# relaxbox.net
KiCad netlist of a schematic drawn in EAGLE
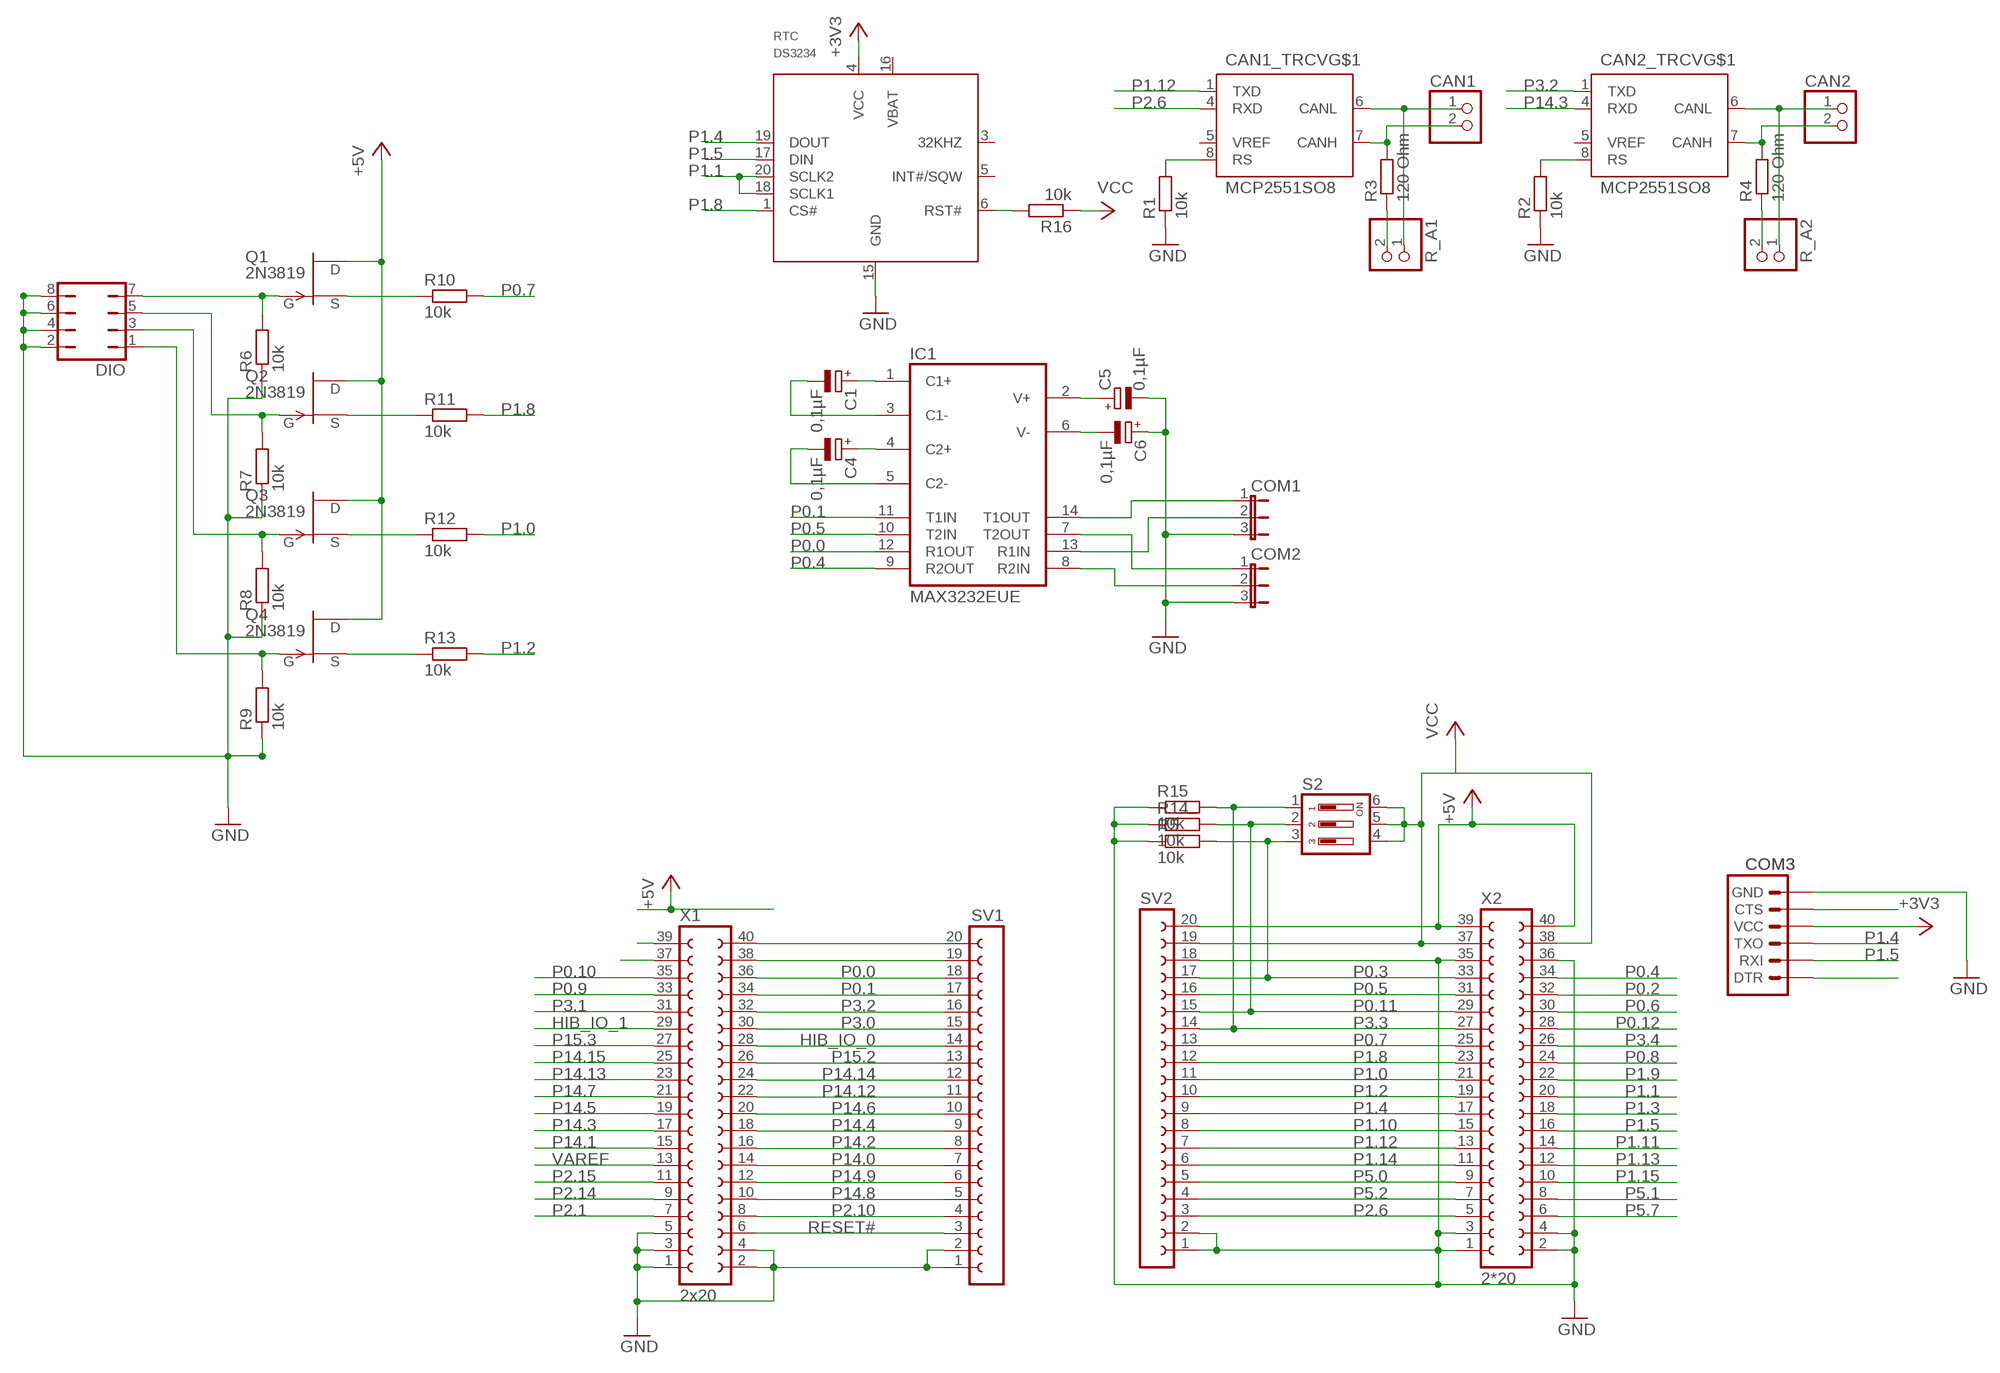
[diagram p0: schematic, sheet 1]

(export (version "E")
  (design (tool "Eeschema 10.0.6"))
  (components
    (comp (ref "C1")
      (value "0,1µF")
      (footprint "eagle-import:E2,5-5")
      (libsource (lib "eagle-import") (part "CPOL-EUE2.5-5"))
    )
    (comp (ref "C4")
      (value "0,1µF")
      (footprint "eagle-import:E2,5-5")
      (libsource (lib "eagle-import") (part "CPOL-EUE2.5-5"))
    )
    (comp (ref "C5")
      (value "0,1µF")
      (footprint "eagle-import:E2,5-5")
      (libsource (lib "eagle-import") (part "CPOL-EUE2.5-5"))
    )
    (comp (ref "C6")
      (value "0,1µF")
      (footprint "eagle-import:E2,5-5")
      (libsource (lib "eagle-import") (part "CPOL-EUE2.5-5"))
    )
    (comp (ref "CAN1")
      (value "PINHD-1X2")
      (footprint "eagle-import:1X02")
      (libsource (lib "eagle-import") (part "PINHD-1X2"))
    )
    (comp (ref "CAN1_TRCV")
      (value "MCP2551SO8")
      (footprint "eagle-import:SO08")
      (libsource (lib "eagle-import") (part "MCP2551SO8"))
    )
    (comp (ref "CAN2")
      (value "PINHD-1X2")
      (footprint "eagle-import:1X02")
      (libsource (lib "eagle-import") (part "PINHD-1X2"))
    )
    (comp (ref "CAN2_TRCV")
      (value "MCP2551SO8")
      (footprint "eagle-import:SO08")
      (libsource (lib "eagle-import") (part "MCP2551SO8"))
    )
    (comp (ref "COM1")
      (value "JP2E")
      (footprint "eagle-import:JP2")
      (libsource (lib "eagle-import") (part "JP2E"))
    )
    (comp (ref "COM2")
      (value "JP2E")
      (footprint "eagle-import:JP2")
      (libsource (lib "eagle-import") (part "JP2E"))
    )
    (comp (ref "COM3")
      (value "SPARKFUN_ARDUINO_SERIAL_PROGRAMPTH")
      (footprint "eagle-import:SPARKFUN_1X06")
      (libsource (lib "eagle-import") (part "SPARKFUN_ARDUINO_SERIAL_PROGRAMPTH"))
    )
    (comp (ref "DIO")
      (value "JP4Q")
      (footprint "eagle-import:JP4Q")
      (libsource (lib "eagle-import") (part "JP4Q"))
    )
    (comp (ref "IC1")
      (value "MAX3232EUE")
      (footprint "eagle-import:TSSOP16")
      (fields (field (name "MF") "MAXIM") (field (name "MPN") "MAX3232EUE+"))
      (libsource (lib "eagle-import") (part "MAX3232UEE"))
    )
    (comp (ref "Q1")
      (value "2N3819")
      (footprint "eagle-import:TO92")
      (libsource (lib "eagle-import") (part "2N3819"))
    )
    (comp (ref "Q2")
      (value "2N3819")
      (footprint "eagle-import:TO92")
      (libsource (lib "eagle-import") (part "2N3819"))
    )
    (comp (ref "Q3")
      (value "2N3819")
      (footprint "eagle-import:TO92")
      (libsource (lib "eagle-import") (part "2N3819"))
    )
    (comp (ref "Q4")
      (value "2N3819")
      (footprint "eagle-import:TO92")
      (libsource (lib "eagle-import") (part "2N3819"))
    )
    (comp (ref "R1")
      (value "10k")
      (footprint "eagle-import:M0805")
      (libsource (lib "eagle-import") (part "R-EU_M0805"))
    )
    (comp (ref "R2")
      (value "10k")
      (footprint "eagle-import:M0805")
      (libsource (lib "eagle-import") (part "R-EU_M0805"))
    )
    (comp (ref "R3")
      (value "120 Ohm")
      (footprint "eagle-import:M0805")
      (libsource (lib "eagle-import") (part "R-EU_M0805"))
    )
    (comp (ref "R4")
      (value "120 Ohm")
      (footprint "eagle-import:M0805")
      (libsource (lib "eagle-import") (part "R-EU_M0805"))
    )
    (comp (ref "R5")
      (value "10k")
      (footprint "eagle-import:M0805")
      (libsource (lib "eagle-import") (part "R-EU_M0805"))
    )
    (comp (ref "R6")
      (value "10k")
      (footprint "eagle-import:M0805")
      (libsource (lib "eagle-import") (part "R-EU_M0805"))
    )
    (comp (ref "R7")
      (value "10k")
      (footprint "eagle-import:M0805")
      (libsource (lib "eagle-import") (part "R-EU_M0805"))
    )
    (comp (ref "R8")
      (value "10k")
      (footprint "eagle-import:M0805")
      (libsource (lib "eagle-import") (part "R-EU_M0805"))
    )
    (comp (ref "R9")
      (value "10k")
      (footprint "eagle-import:M0805")
      (libsource (lib "eagle-import") (part "R-EU_M0805"))
    )
    (comp (ref "R10")
      (value "10k")
      (footprint "eagle-import:M0805")
      (libsource (lib "eagle-import") (part "R-EU_M0805"))
    )
    (comp (ref "R11")
      (value "10k")
      (footprint "eagle-import:M0805")
      (libsource (lib "eagle-import") (part "R-EU_M0805"))
    )
    (comp (ref "R12")
      (value "10k")
      (footprint "eagle-import:M0805")
      (libsource (lib "eagle-import") (part "R-EU_M0805"))
    )
    (comp (ref "R13")
      (value "10k")
      (footprint "eagle-import:M0805")
      (libsource (lib "eagle-import") (part "R-EU_M0805"))
    )
    (comp (ref "R14")
      (value "10k")
      (footprint "eagle-import:M0805")
      (libsource (lib "eagle-import") (part "R-EU_M0805"))
    )
    (comp (ref "R15")
      (value "10k")
      (footprint "eagle-import:M0805")
      (libsource (lib "eagle-import") (part "R-EU_M0805"))
    )
    (comp (ref "R16")
      (value "10k")
      (footprint "eagle-import:M0805")
      (libsource (lib "eagle-import") (part "R-EU_M0805"))
    )
    (comp (ref "RTC")
      (value "DS3234")
      (footprint "eagle-import:SO-20DW")
      (libsource (lib "eagle-import") (part "DS3234"))
    )
    (comp (ref "R_A1")
      (value "PINHD-1X2")
      (footprint "eagle-import:1X02")
      (libsource (lib "eagle-import") (part "PINHD-1X2"))
    )
    (comp (ref "R_A2")
      (value "PINHD-1X2")
      (footprint "eagle-import:1X02")
      (libsource (lib "eagle-import") (part "PINHD-1X2"))
    )
    (comp (ref "S2")
      (value "DIP03YL")
      (footprint "eagle-import:DIP03YL")
      (libsource (lib "eagle-import") (part "DIP03YL"))
    )
    (comp (ref "SV1")
      (value "FE20-1")
      (footprint "eagle-import:FE20")
      (libsource (lib "eagle-import") (part "FE20-1"))
    )
    (comp (ref "SV2")
      (value "FE20-1")
      (footprint "eagle-import:FE20")
      (libsource (lib "eagle-import") (part "FE20-1"))
    )
    (comp (ref "X1")
      (value "2x20")
      (footprint "eagle-import:FE20-2")
      (libsource (lib "eagle-import") (part "FE20-2"))
    )
    (comp (ref "X2")
      (value "2*20")
      (footprint "eagle-import:FE20-2")
      (libsource (lib "eagle-import") (part "FE20-2"))
    )
  )
  (nets
    (net (code "1") (name "+3V3") (class "Default")
      (node (ref "COM3") (pin "4") (pinfunction "VCC_4") (pintype "passive"))
      (node (ref "RTC") (pin "4") (pinfunction "VCC_4") (pintype "bidirectional"))
    )
    (net (code "2") (name "+5V") (class "Default")
      (node (ref "Q1") (pin "1") (pinfunction "D_1") (pintype "passive"))
      (node (ref "Q2") (pin "1") (pinfunction "D_1") (pintype "passive"))
      (node (ref "Q3") (pin "1") (pinfunction "D_1") (pintype "passive"))
      (node (ref "Q4") (pin "1") (pinfunction "D_1") (pintype "passive"))
      (node (ref "SV2") (pin "20") (pinfunction "20_20") (pintype "passive"))
      (node (ref "X2") (pin "39") (pinfunction "39_39") (pintype "passive"))
      (node (ref "X2") (pin "40") (pinfunction "40_40") (pintype "passive"))
    )
    (net (code "3") (name "/HIB_IO_0") (class "Default")
      (node (ref "SV1") (pin "14") (pinfunction "14_14") (pintype "passive"))
      (node (ref "X1") (pin "28") (pinfunction "28_28") (pintype "passive"))
    )
    (net (code "4") (name "/HIB_IO_1") (class "Default")
      (node (ref "X1") (pin "29") (pinfunction "29_29") (pintype "passive"))
    )
    (net (code "5") (name "/P0.0") (class "Default")
      (node (ref "IC1") (pin "12") (pinfunction "R1OUT_12") (pintype "output"))
      (node (ref "SV1") (pin "18") (pinfunction "18_18") (pintype "passive"))
      (node (ref "X1") (pin "36") (pinfunction "36_36") (pintype "passive"))
    )
    (net (code "6") (name "/P0.1") (class "Default")
      (node (ref "IC1") (pin "11") (pinfunction "T1IN_11") (pintype "input"))
      (node (ref "SV1") (pin "17") (pinfunction "17_17") (pintype "passive"))
      (node (ref "X1") (pin "34") (pinfunction "34_34") (pintype "passive"))
    )
    (net (code "7") (name "/P0.2") (class "Default")
      (node (ref "X2") (pin "32") (pinfunction "32_32") (pintype "passive"))
    )
    (net (code "8") (name "/P0.3") (class "Default")
      (node (ref "R5") (pin "2") (pinfunction "2_2") (pintype "passive"))
      (node (ref "S2") (pin "3") (pinfunction "3_3") (pintype "passive"))
      (node (ref "SV2") (pin "17") (pinfunction "17_17") (pintype "passive"))
      (node (ref "X2") (pin "33") (pinfunction "33_33") (pintype "passive"))
    )
    (net (code "9") (name "/P0.4") (class "Default")
      (node (ref "IC1") (pin "9") (pinfunction "R2OUT_9") (pintype "output"))
      (node (ref "X2") (pin "34") (pinfunction "34_34") (pintype "passive"))
    )
    (net (code "10") (name "/P0.5") (class "Default")
      (node (ref "IC1") (pin "10") (pinfunction "T2IN_10") (pintype "input"))
      (node (ref "SV2") (pin "16") (pinfunction "16_16") (pintype "passive"))
      (node (ref "X2") (pin "31") (pinfunction "31_31") (pintype "passive"))
    )
    (net (code "11") (name "/P0.6") (class "Default")
      (node (ref "X2") (pin "30") (pinfunction "30_30") (pintype "passive"))
    )
    (net (code "12") (name "/P0.7") (class "Default")
      (node (ref "R10") (pin "2") (pinfunction "2_2") (pintype "passive"))
      (node (ref "SV2") (pin "13") (pinfunction "13_13") (pintype "passive"))
      (node (ref "X2") (pin "25") (pinfunction "25_25") (pintype "passive"))
    )
    (net (code "13") (name "/P0.8") (class "Default")
      (node (ref "X2") (pin "24") (pinfunction "24_24") (pintype "passive"))
    )
    (net (code "14") (name "/P0.9") (class "Default")
      (node (ref "X1") (pin "33") (pinfunction "33_33") (pintype "passive"))
    )
    (net (code "15") (name "/P0.10") (class "Default")
      (node (ref "X1") (pin "35") (pinfunction "35_35") (pintype "passive"))
    )
    (net (code "16") (name "/P0.11") (class "Default")
      (node (ref "R14") (pin "2") (pinfunction "2_2") (pintype "passive"))
      (node (ref "S2") (pin "2") (pinfunction "2_2") (pintype "passive"))
      (node (ref "SV2") (pin "15") (pinfunction "15_15") (pintype "passive"))
      (node (ref "X2") (pin "29") (pinfunction "29_29") (pintype "passive"))
    )
    (net (code "17") (name "/P0.12") (class "Default")
      (node (ref "X2") (pin "28") (pinfunction "28_28") (pintype "passive"))
    )
    (net (code "18") (name "/P1.0") (class "Default")
      (node (ref "R12") (pin "2") (pinfunction "2_2") (pintype "passive"))
      (node (ref "SV2") (pin "11") (pinfunction "11_11") (pintype "passive"))
      (node (ref "X2") (pin "21") (pinfunction "21_21") (pintype "passive"))
    )
    (net (code "19") (name "/P1.1") (class "Default")
      (node (ref "RTC") (pin "18") (pinfunction "SCLK1_18") (pintype "bidirectional"))
      (node (ref "RTC") (pin "20") (pinfunction "SCLK2_20") (pintype "bidirectional"))
      (node (ref "X2") (pin "20") (pinfunction "20_20") (pintype "passive"))
    )
    (net (code "20") (name "/P1.2") (class "Default")
      (node (ref "R13") (pin "2") (pinfunction "2_2") (pintype "passive"))
      (node (ref "SV2") (pin "10") (pinfunction "10_10") (pintype "passive"))
      (node (ref "X2") (pin "19") (pinfunction "19_19") (pintype "passive"))
    )
    (net (code "21") (name "/P1.3") (class "Default")
      (node (ref "X2") (pin "18") (pinfunction "18_18") (pintype "passive"))
    )
    (net (code "22") (name "/P1.4") (class "Default")
      (node (ref "COM3") (pin "3") (pinfunction "TXO_3") (pintype "passive"))
      (node (ref "RTC") (pin "19") (pinfunction "DOUT_19") (pintype "bidirectional"))
      (node (ref "SV2") (pin "9") (pinfunction "9_9") (pintype "passive"))
      (node (ref "X2") (pin "17") (pinfunction "17_17") (pintype "passive"))
    )
    (net (code "23") (name "/P1.5") (class "Default")
      (node (ref "COM3") (pin "2") (pinfunction "RXI_2") (pintype "passive"))
      (node (ref "RTC") (pin "17") (pinfunction "DIN_17") (pintype "bidirectional"))
      (node (ref "X2") (pin "16") (pinfunction "16_16") (pintype "passive"))
    )
    (net (code "24") (name "/P1.8") (class "Default")
      (node (ref "R11") (pin "2") (pinfunction "2_2") (pintype "passive"))
      (node (ref "RTC") (pin "1") (pinfunction "CS#_1") (pintype "bidirectional"))
      (node (ref "SV2") (pin "12") (pinfunction "12_12") (pintype "passive"))
      (node (ref "X2") (pin "23") (pinfunction "23_23") (pintype "passive"))
    )
    (net (code "25") (name "/P1.9") (class "Default")
      (node (ref "X2") (pin "22") (pinfunction "22_22") (pintype "passive"))
    )
    (net (code "26") (name "/P1.10") (class "Default")
      (node (ref "SV2") (pin "8") (pinfunction "8_8") (pintype "passive"))
      (node (ref "X2") (pin "15") (pinfunction "15_15") (pintype "passive"))
    )
    (net (code "27") (name "/P1.11") (class "Default")
      (node (ref "X2") (pin "14") (pinfunction "14_14") (pintype "passive"))
    )
    (net (code "28") (name "/P1.12") (class "Default")
      (node (ref "CAN1_TRCV") (pin "1") (pinfunction "TXD_1") (pintype "bidirectional"))
      (node (ref "SV2") (pin "7") (pinfunction "7_7") (pintype "passive"))
      (node (ref "X2") (pin "13") (pinfunction "13_13") (pintype "passive"))
    )
    (net (code "29") (name "/P1.13") (class "Default")
      (node (ref "X2") (pin "12") (pinfunction "12_12") (pintype "passive"))
    )
    (net (code "30") (name "/P1.14") (class "Default")
      (node (ref "SV2") (pin "6") (pinfunction "6_6") (pintype "passive"))
      (node (ref "X2") (pin "11") (pinfunction "11_11") (pintype "passive"))
    )
    (net (code "31") (name "/P1.15") (class "Default")
      (node (ref "X2") (pin "10") (pinfunction "10_10") (pintype "passive"))
    )
    (net (code "32") (name "/P2.1") (class "Default")
      (node (ref "X1") (pin "7") (pinfunction "7_7") (pintype "passive"))
    )
    (net (code "33") (name "/P2.6") (class "Default")
      (node (ref "CAN1_TRCV") (pin "4") (pinfunction "RXD_4") (pintype "bidirectional"))
      (node (ref "SV2") (pin "3") (pinfunction "3_3") (pintype "passive"))
      (node (ref "X2") (pin "5") (pinfunction "5_5") (pintype "passive"))
    )
    (net (code "34") (name "/P2.10") (class "Default")
      (node (ref "SV1") (pin "4") (pinfunction "4_4") (pintype "passive"))
      (node (ref "X1") (pin "8") (pinfunction "8_8") (pintype "passive"))
    )
    (net (code "35") (name "/P2.14") (class "Default")
      (node (ref "X1") (pin "9") (pinfunction "9_9") (pintype "passive"))
    )
    (net (code "36") (name "/P2.15") (class "Default")
      (node (ref "X1") (pin "11") (pinfunction "11_11") (pintype "passive"))
    )
    (net (code "37") (name "/P3.0") (class "Default")
      (node (ref "SV1") (pin "15") (pinfunction "15_15") (pintype "passive"))
      (node (ref "X1") (pin "30") (pinfunction "30_30") (pintype "passive"))
    )
    (net (code "38") (name "/P3.1") (class "Default")
      (node (ref "X1") (pin "31") (pinfunction "31_31") (pintype "passive"))
    )
    (net (code "39") (name "/P3.2") (class "Default")
      (node (ref "CAN2_TRCV") (pin "1") (pinfunction "TXD_1") (pintype "bidirectional"))
      (node (ref "SV1") (pin "16") (pinfunction "16_16") (pintype "passive"))
      (node (ref "X1") (pin "32") (pinfunction "32_32") (pintype "passive"))
    )
    (net (code "40") (name "/P3.3") (class "Default")
      (node (ref "R15") (pin "2") (pinfunction "2_2") (pintype "passive"))
      (node (ref "S2") (pin "1") (pinfunction "1_1") (pintype "passive"))
      (node (ref "SV2") (pin "14") (pinfunction "14_14") (pintype "passive"))
      (node (ref "X2") (pin "27") (pinfunction "27_27") (pintype "passive"))
    )
    (net (code "41") (name "/P3.4") (class "Default")
      (node (ref "X2") (pin "26") (pinfunction "26_26") (pintype "passive"))
    )
    (net (code "42") (name "/P5.0") (class "Default")
      (node (ref "SV2") (pin "5") (pinfunction "5_5") (pintype "passive"))
      (node (ref "X2") (pin "9") (pinfunction "9_9") (pintype "passive"))
    )
    (net (code "43") (name "/P5.1") (class "Default")
      (node (ref "X2") (pin "8") (pinfunction "8_8") (pintype "passive"))
    )
    (net (code "44") (name "/P5.2") (class "Default")
      (node (ref "SV2") (pin "4") (pinfunction "4_4") (pintype "passive"))
      (node (ref "X2") (pin "7") (pinfunction "7_7") (pintype "passive"))
    )
    (net (code "45") (name "/P5.7") (class "Default")
      (node (ref "X2") (pin "6") (pinfunction "6_6") (pintype "passive"))
    )
    (net (code "46") (name "/P14.0") (class "Default")
      (node (ref "SV1") (pin "7") (pinfunction "7_7") (pintype "passive"))
      (node (ref "X1") (pin "14") (pinfunction "14_14") (pintype "passive"))
    )
    (net (code "47") (name "/P14.1") (class "Default")
      (node (ref "X1") (pin "15") (pinfunction "15_15") (pintype "passive"))
    )
    (net (code "48") (name "/P14.2") (class "Default")
      (node (ref "SV1") (pin "8") (pinfunction "8_8") (pintype "passive"))
      (node (ref "X1") (pin "16") (pinfunction "16_16") (pintype "passive"))
    )
    (net (code "49") (name "/P14.3") (class "Default")
      (node (ref "CAN2_TRCV") (pin "4") (pinfunction "RXD_4") (pintype "bidirectional"))
      (node (ref "X1") (pin "17") (pinfunction "17_17") (pintype "passive"))
    )
    (net (code "50") (name "/P14.4") (class "Default")
      (node (ref "SV1") (pin "9") (pinfunction "9_9") (pintype "passive"))
      (node (ref "X1") (pin "18") (pinfunction "18_18") (pintype "passive"))
    )
    (net (code "51") (name "/P14.5") (class "Default")
      (node (ref "X1") (pin "19") (pinfunction "19_19") (pintype "passive"))
    )
    (net (code "52") (name "/P14.6") (class "Default")
      (node (ref "SV1") (pin "10") (pinfunction "10_10") (pintype "passive"))
      (node (ref "X1") (pin "20") (pinfunction "20_20") (pintype "passive"))
    )
    (net (code "53") (name "/P14.7") (class "Default")
      (node (ref "X1") (pin "21") (pinfunction "21_21") (pintype "passive"))
    )
    (net (code "54") (name "/P14.8") (class "Default")
      (node (ref "SV1") (pin "5") (pinfunction "5_5") (pintype "passive"))
      (node (ref "X1") (pin "10") (pinfunction "10_10") (pintype "passive"))
    )
    (net (code "55") (name "/P14.9") (class "Default")
      (node (ref "SV1") (pin "6") (pinfunction "6_6") (pintype "passive"))
      (node (ref "X1") (pin "12") (pinfunction "12_12") (pintype "passive"))
    )
    (net (code "56") (name "/P14.12") (class "Default")
      (node (ref "SV1") (pin "11") (pinfunction "11_11") (pintype "passive"))
      (node (ref "X1") (pin "22") (pinfunction "22_22") (pintype "passive"))
    )
    (net (code "57") (name "/P14.13") (class "Default")
      (node (ref "X1") (pin "23") (pinfunction "23_23") (pintype "passive"))
    )
    (net (code "58") (name "/P14.14") (class "Default")
      (node (ref "SV1") (pin "12") (pinfunction "12_12") (pintype "passive"))
      (node (ref "X1") (pin "24") (pinfunction "24_24") (pintype "passive"))
    )
    (net (code "59") (name "/P14.15") (class "Default")
      (node (ref "X1") (pin "25") (pinfunction "25_25") (pintype "passive"))
    )
    (net (code "60") (name "/P15.2") (class "Default")
      (node (ref "SV1") (pin "13") (pinfunction "13_13") (pintype "passive"))
      (node (ref "X1") (pin "26") (pinfunction "26_26") (pintype "passive"))
    )
    (net (code "61") (name "/P15.3") (class "Default")
      (node (ref "X1") (pin "27") (pinfunction "27_27") (pintype "passive"))
    )
    (net (code "62") (name "/RESET#") (class "Default")
      (node (ref "SV1") (pin "3") (pinfunction "3_3") (pintype "passive"))
      (node (ref "X1") (pin "6") (pinfunction "6_6") (pintype "passive"))
    )
    (net (code "63") (name "/VAREF") (class "Default")
      (node (ref "X1") (pin "13") (pinfunction "13_13") (pintype "passive"))
    )
    (net (code "64") (name "GND") (class "Default")
      (node (ref "C5") (pin "-") (pinfunction "-_-") (pintype "passive"))
      (node (ref "C6") (pin "+") (pinfunction "+_+") (pintype "passive"))
      (node (ref "COM1") (pin "3") (pinfunction "3_3") (pintype "passive"))
      (node (ref "COM2") (pin "3") (pinfunction "3_3") (pintype "passive"))
      (node (ref "COM3") (pin "6") (pinfunction "GND_6") (pintype "passive"))
      (node (ref "DIO") (pin "2") (pinfunction "2_2") (pintype "passive"))
      (node (ref "DIO") (pin "4") (pinfunction "4_4") (pintype "passive"))
      (node (ref "DIO") (pin "6") (pinfunction "6_6") (pintype "passive"))
      (node (ref "DIO") (pin "8") (pinfunction "8_8") (pintype "passive"))
      (node (ref "R1") (pin "1") (pinfunction "1_1") (pintype "passive"))
      (node (ref "R14") (pin "1") (pinfunction "1_1") (pintype "passive"))
      (node (ref "R15") (pin "1") (pinfunction "1_1") (pintype "passive"))
      (node (ref "R2") (pin "1") (pinfunction "1_1") (pintype "passive"))
      (node (ref "R5") (pin "1") (pinfunction "1_1") (pintype "passive"))
      (node (ref "R6") (pin "1") (pinfunction "1_1") (pintype "passive"))
      (node (ref "R7") (pin "1") (pinfunction "1_1") (pintype "passive"))
      (node (ref "R8") (pin "1") (pinfunction "1_1") (pintype "passive"))
      (node (ref "R9") (pin "1") (pinfunction "1_1") (pintype "passive"))
      (node (ref "RTC") (pin "15") (pinfunction "GND_15") (pintype "bidirectional"))
      (node (ref "SV1") (pin "1") (pinfunction "1_1") (pintype "passive"))
      (node (ref "SV1") (pin "2") (pinfunction "2_2") (pintype "passive"))
      (node (ref "SV2") (pin "1") (pinfunction "1_1") (pintype "passive"))
      (node (ref "SV2") (pin "18") (pinfunction "18_18") (pintype "passive"))
      (node (ref "SV2") (pin "2") (pinfunction "2_2") (pintype "passive"))
      (node (ref "X1") (pin "1") (pinfunction "1_1") (pintype "passive"))
      (node (ref "X1") (pin "2") (pinfunction "2_2") (pintype "passive"))
      (node (ref "X1") (pin "3") (pinfunction "3_3") (pintype "passive"))
      (node (ref "X1") (pin "4") (pinfunction "4_4") (pintype "passive"))
      (node (ref "X1") (pin "5") (pinfunction "5_5") (pintype "passive"))
      (node (ref "X2") (pin "1") (pinfunction "1_1") (pintype "passive"))
      (node (ref "X2") (pin "2") (pinfunction "2_2") (pintype "passive"))
      (node (ref "X2") (pin "3") (pinfunction "3_3") (pintype "passive"))
      (node (ref "X2") (pin "35") (pinfunction "35_35") (pintype "passive"))
      (node (ref "X2") (pin "36") (pinfunction "36_36") (pintype "passive"))
      (node (ref "X2") (pin "4") (pinfunction "4_4") (pintype "passive"))
    )
    (net (code "65") (name "Net-(CAN1_TRCVA-CANH)") (class "Default")
      (node (ref "CAN1") (pin "2") (pinfunction "2_2") (pintype "passive"))
      (node (ref "CAN1_TRCV") (pin "7") (pinfunction "CANH_7") (pintype "bidirectional"))
      (node (ref "R3") (pin "2") (pinfunction "2_2") (pintype "passive"))
    )
    (net (code "66") (name "Net-(CAN1_TRCVA-CANL)") (class "Default")
      (node (ref "CAN1") (pin "1") (pinfunction "1_1") (pintype "passive"))
      (node (ref "CAN1_TRCV") (pin "6") (pinfunction "CANL_6") (pintype "bidirectional"))
      (node (ref "R_A1") (pin "1") (pinfunction "1_1") (pintype "passive"))
    )
    (net (code "67") (name "Net-(CAN1_TRCVA-RS)") (class "Default")
      (node (ref "CAN1_TRCV") (pin "8") (pinfunction "RS_8") (pintype "bidirectional"))
      (node (ref "R1") (pin "2") (pinfunction "2_2") (pintype "passive"))
    )
    (net (code "68") (name "Net-(CAN2_TRCVA-CANH)") (class "Default")
      (node (ref "CAN2") (pin "2") (pinfunction "2_2") (pintype "passive"))
      (node (ref "CAN2_TRCV") (pin "7") (pinfunction "CANH_7") (pintype "bidirectional"))
      (node (ref "R4") (pin "2") (pinfunction "2_2") (pintype "passive"))
    )
    (net (code "69") (name "Net-(CAN2_TRCVA-CANL)") (class "Default")
      (node (ref "CAN2") (pin "1") (pinfunction "1_1") (pintype "passive"))
      (node (ref "CAN2_TRCV") (pin "6") (pinfunction "CANL_6") (pintype "bidirectional"))
      (node (ref "R_A2") (pin "1") (pinfunction "1_1") (pintype "passive"))
    )
    (net (code "70") (name "Net-(CAN2_TRCVA-RS)") (class "Default")
      (node (ref "CAN2_TRCV") (pin "8") (pinfunction "RS_8") (pintype "bidirectional"))
      (node (ref "R2") (pin "2") (pinfunction "2_2") (pintype "passive"))
    )
    (net (code "71") (name "Net-(IC1A-C1+)") (class "Default")
      (node (ref "C1") (pin "+") (pinfunction "+_+") (pintype "passive"))
      (node (ref "IC1") (pin "1") (pinfunction "C1+_1") (pintype "bidirectional"))
    )
    (net (code "72") (name "Net-(IC1A-C1-)") (class "Default")
      (node (ref "C1") (pin "-") (pinfunction "-_-") (pintype "passive"))
      (node (ref "IC1") (pin "3") (pinfunction "C1-_3") (pintype "bidirectional"))
    )
    (net (code "73") (name "Net-(IC1A-C2+)") (class "Default")
      (node (ref "C4") (pin "+") (pinfunction "+_+") (pintype "passive"))
      (node (ref "IC1") (pin "4") (pinfunction "C2+_4") (pintype "bidirectional"))
    )
    (net (code "74") (name "Net-(IC1A-C2-)") (class "Default")
      (node (ref "C4") (pin "-") (pinfunction "-_-") (pintype "passive"))
      (node (ref "IC1") (pin "5") (pinfunction "C2-_5") (pintype "bidirectional"))
    )
    (net (code "75") (name "Net-(IC1A-R1IN)") (class "Default")
      (node (ref "COM1") (pin "2") (pinfunction "2_2") (pintype "passive"))
      (node (ref "IC1") (pin "13") (pinfunction "R1IN_13") (pintype "input"))
    )
    (net (code "76") (name "Net-(IC1A-R2IN)") (class "Default")
      (node (ref "COM2") (pin "2") (pinfunction "2_2") (pintype "passive"))
      (node (ref "IC1") (pin "8") (pinfunction "R2IN_8") (pintype "input"))
    )
    (net (code "77") (name "Net-(IC1A-T1OUT)") (class "Default")
      (node (ref "COM1") (pin "1") (pinfunction "1_1") (pintype "passive"))
      (node (ref "IC1") (pin "14") (pinfunction "T1OUT_14") (pintype "output"))
    )
    (net (code "78") (name "Net-(IC1A-T2OUT)") (class "Default")
      (node (ref "COM2") (pin "1") (pinfunction "1_1") (pintype "passive"))
      (node (ref "IC1") (pin "7") (pinfunction "T2OUT_7") (pintype "output"))
    )
    (net (code "79") (name "Net-(IC1A-V+)") (class "Default")
      (node (ref "C5") (pin "+") (pinfunction "+_+") (pintype "passive"))
      (node (ref "IC1") (pin "2") (pinfunction "V+_2") (pintype "bidirectional"))
    )
    (net (code "80") (name "Net-(IC1A-V-)") (class "Default")
      (node (ref "C6") (pin "-") (pinfunction "-_-") (pintype "passive"))
      (node (ref "IC1") (pin "6") (pinfunction "V-_6") (pintype "bidirectional"))
    )
    (net (code "81") (name "Net-(Q1-G)") (class "Default")
      (node (ref "DIO") (pin "7") (pinfunction "7_7") (pintype "passive"))
      (node (ref "Q1") (pin "2") (pinfunction "G_2") (pintype "passive"))
      (node (ref "R6") (pin "2") (pinfunction "2_2") (pintype "passive"))
    )
    (net (code "82") (name "Net-(Q1-S)") (class "Default")
      (node (ref "Q1") (pin "3") (pinfunction "S_3") (pintype "passive"))
      (node (ref "R10") (pin "1") (pinfunction "1_1") (pintype "passive"))
    )
    (net (code "83") (name "Net-(Q2-G)") (class "Default")
      (node (ref "DIO") (pin "5") (pinfunction "5_5") (pintype "passive"))
      (node (ref "Q2") (pin "2") (pinfunction "G_2") (pintype "passive"))
      (node (ref "R7") (pin "2") (pinfunction "2_2") (pintype "passive"))
    )
    (net (code "84") (name "Net-(Q2-S)") (class "Default")
      (node (ref "Q2") (pin "3") (pinfunction "S_3") (pintype "passive"))
      (node (ref "R11") (pin "1") (pinfunction "1_1") (pintype "passive"))
    )
    (net (code "85") (name "Net-(Q3-G)") (class "Default")
      (node (ref "DIO") (pin "3") (pinfunction "3_3") (pintype "passive"))
      (node (ref "Q3") (pin "2") (pinfunction "G_2") (pintype "passive"))
      (node (ref "R8") (pin "2") (pinfunction "2_2") (pintype "passive"))
    )
    (net (code "86") (name "Net-(Q3-S)") (class "Default")
      (node (ref "Q3") (pin "3") (pinfunction "S_3") (pintype "passive"))
      (node (ref "R12") (pin "1") (pinfunction "1_1") (pintype "passive"))
    )
    (net (code "87") (name "Net-(Q4-G)") (class "Default")
      (node (ref "DIO") (pin "1") (pinfunction "1_1") (pintype "passive"))
      (node (ref "Q4") (pin "2") (pinfunction "G_2") (pintype "passive"))
      (node (ref "R9") (pin "2") (pinfunction "2_2") (pintype "passive"))
    )
    (net (code "88") (name "Net-(Q4-S)") (class "Default")
      (node (ref "Q4") (pin "3") (pinfunction "S_3") (pintype "passive"))
      (node (ref "R13") (pin "1") (pinfunction "1_1") (pintype "passive"))
    )
    (net (code "89") (name "Net-(R3-Pad1)") (class "Default")
      (node (ref "R3") (pin "1") (pinfunction "1_1") (pintype "passive"))
      (node (ref "R_A1") (pin "2") (pinfunction "2_2") (pintype "passive"))
    )
    (net (code "90") (name "Net-(R4-Pad1)") (class "Default")
      (node (ref "R4") (pin "1") (pinfunction "1_1") (pintype "passive"))
      (node (ref "R_A2") (pin "2") (pinfunction "2_2") (pintype "passive"))
    )
    (net (code "91") (name "Net-(RTC-RST#)") (class "Default")
      (node (ref "R16") (pin "2") (pinfunction "2_2") (pintype "passive"))
      (node (ref "RTC") (pin "6") (pinfunction "RST#_6") (pintype "bidirectional"))
    )
    (net (code "92") (name "Net-(SV1-Pad19)") (class "Default")
      (node (ref "SV1") (pin "19") (pinfunction "19_19") (pintype "passive"))
      (node (ref "X1") (pin "38") (pinfunction "38_38") (pintype "passive"))
    )
    (net (code "93") (name "Net-(SV1-Pad20)") (class "Default")
      (node (ref "SV1") (pin "20") (pinfunction "20_20") (pintype "passive"))
      (node (ref "X1") (pin "40") (pinfunction "40_40") (pintype "passive"))
    )
    (net (code "94") (name "VCC") (class "Default")
      (node (ref "R16") (pin "1") (pinfunction "1_1") (pintype "passive"))
      (node (ref "S2") (pin "4") (pinfunction "4_4") (pintype "passive"))
      (node (ref "S2") (pin "5") (pinfunction "5_5") (pintype "passive"))
      (node (ref "S2") (pin "6") (pinfunction "6_6") (pintype "passive"))
      (node (ref "SV2") (pin "19") (pinfunction "19_19") (pintype "passive"))
      (node (ref "X2") (pin "37") (pinfunction "37_37") (pintype "passive"))
      (node (ref "X2") (pin "38") (pinfunction "38_38") (pintype "passive"))
    )
    (net (code "95") (name "unconnected-(CAN1_TRCVA-VREF-Pad5)") (class "Default")
      (node (ref "CAN1_TRCV") (pin "5") (pinfunction "VREF_5") (pintype "bidirectional"))
    )
    (net (code "96") (name "unconnected-(CAN2_TRCVA-VREF-Pad5)") (class "Default")
      (node (ref "CAN2_TRCV") (pin "5") (pinfunction "VREF_5") (pintype "bidirectional"))
    )
    (net (code "97") (name "unconnected-(COM3-CTS-Pad5)") (class "Default")
      (node (ref "COM3") (pin "5") (pinfunction "CTS_5") (pintype "passive"))
    )
    (net (code "98") (name "unconnected-(COM3-DTR-Pad1)") (class "Default")
      (node (ref "COM3") (pin "1") (pinfunction "DTR_1") (pintype "passive"))
    )
    (net (code "99") (name "unconnected-(RTC-32KHZ-Pad3)") (class "Default")
      (node (ref "RTC") (pin "3") (pinfunction "32KHZ_3") (pintype "bidirectional"))
    )
    (net (code "100") (name "unconnected-(RTC-INT#{slash}SQW-Pad5)") (class "Default")
      (node (ref "RTC") (pin "5") (pinfunction "INT#/SQW_5") (pintype "bidirectional"))
    )
    (net (code "101") (name "unconnected-(RTC-VBAT-Pad16)") (class "Default")
      (node (ref "RTC") (pin "16") (pinfunction "VBAT_16") (pintype "bidirectional"))
    )
    (net (code "102") (name "unconnected-(X1-Pad37)") (class "Default")
      (node (ref "X1") (pin "37") (pinfunction "37_37") (pintype "passive"))
    )
    (net (code "103") (name "unconnected-(X1-Pad39)") (class "Default")
      (node (ref "X1") (pin "39") (pinfunction "39_39") (pintype "passive"))
    )
  )
)
